# AstableMultivibrator-PNP-old.net
KiCad netlist of a schematic drawn in EAGLE
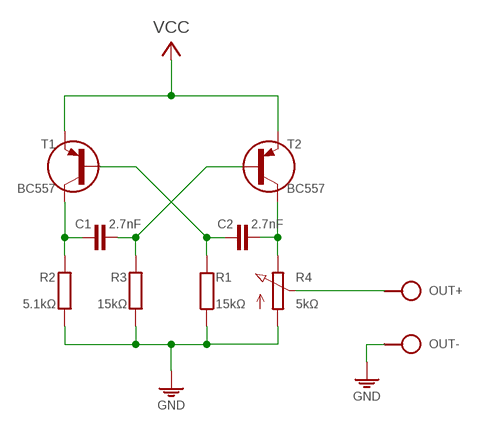
[diagram p0: schematic, sheet 1]

(export (version "E")
  (design (tool "Eeschema 10.0.6"))
  (components
    (comp (ref "C1")
      (value "2.7nF")
      (footprint "eagle-import:C050-020X044")
      (libsource (lib "eagle-import") (part "C-H050-020X044"))
    )
    (comp (ref "C2")
      (value "2.7nF")
      (footprint "eagle-import:C050-020X044")
      (libsource (lib "eagle-import") (part "C-H050-020X044"))
    )
    (comp (ref "J1")
      (value "VCC_GNDPWR-L")
      (footprint "eagle-import:PWR-L")
      (libsource (lib "eagle-import") (part "VCC_GNDPWR-L"))
    )
    (comp (ref "OUT")
      (value "SPAD+--+")
      (footprint "eagle-import:SPAD-+")
      (libsource (lib "eagle-import") (part "SPAD+--+"))
    )
    (comp (ref "R1")
      (value "15kΩ")
      (footprint "eagle-import:0202_5-V")
      (libsource (lib "eagle-import") (part "R0202/5-V"))
    )
    (comp (ref "R2")
      (value "5.1kΩ")
      (footprint "eagle-import:0202_5-V")
      (libsource (lib "eagle-import") (part "R0202/5-V"))
    )
    (comp (ref "R3")
      (value "15kΩ")
      (footprint "eagle-import:0202_5-V")
      (libsource (lib "eagle-import") (part "R0202/5-V"))
    )
    (comp (ref "R4")
      (value "5kΩ")
      (footprint "eagle-import:POT-V")
      (libsource (lib "eagle-import") (part "POT-V"))
    )
    (comp (ref "T1")
      (value "BC557")
      (footprint "eagle-import:TO92-CBE")
      (libsource (lib "eagle-import") (part "BC557CBE"))
    )
    (comp (ref "T2")
      (value "BC557")
      (footprint "eagle-import:TO92-CBE")
      (libsource (lib "eagle-import") (part "BC557CBE"))
    )
  )
  (nets
    (net (code "1") (name "GND") (class "Default")
      (node (ref "J1") (pin "1") (pinfunction "GND_1") (pintype "power_in"))
      (node (ref "OUT") (pin "1") (pinfunction "P$1_1") (pintype "passive"))
      (node (ref "R1") (pin "1") (pinfunction "2_1") (pintype "passive"))
      (node (ref "R2") (pin "1") (pinfunction "2_1") (pintype "passive"))
      (node (ref "R3") (pin "1") (pinfunction "2_1") (pintype "passive"))
      (node (ref "R4") (pin "A") (pinfunction "A_A") (pintype "passive"))
    )
    (net (code "2") (name "Net-(C2-Pad2)") (class "Default")
      (node (ref "C2") (pin "2") (pinfunction "2_2") (pintype "passive"))
      (node (ref "R4") (pin "E") (pinfunction "E_E") (pintype "passive"))
      (node (ref "T2") (pin "C") (pinfunction "C_C") (pintype "passive"))
    )
    (net (code "3") (name "Net-(J1A-VCC)") (class "Default")
      (node (ref "J1") (pin "2") (pinfunction "VCC_2") (pintype "power_in"))
      (node (ref "T1") (pin "E") (pinfunction "E_E") (pintype "passive"))
      (node (ref "T2") (pin "E") (pinfunction "E_E") (pintype "passive"))
    )
    (net (code "4") (name "Net-(OUTA-P$1)") (class "Default")
      (node (ref "OUT") (pin "2") (pinfunction "P$1_2") (pintype "passive"))
      (node (ref "R4") (pin "S") (pinfunction "S_S") (pintype "passive"))
    )
    (net (code "5") (name "Net-(R1-1)") (class "Default")
      (node (ref "C2") (pin "1") (pinfunction "1_1") (pintype "passive"))
      (node (ref "R1") (pin "2") (pinfunction "1_2") (pintype "passive"))
      (node (ref "T1") (pin "B") (pinfunction "B_B") (pintype "passive"))
    )
    (net (code "6") (name "Net-(R2-1)") (class "Default")
      (node (ref "C1") (pin "1") (pinfunction "1_1") (pintype "passive"))
      (node (ref "R2") (pin "2") (pinfunction "1_2") (pintype "passive"))
      (node (ref "T1") (pin "C") (pinfunction "C_C") (pintype "passive"))
    )
    (net (code "7") (name "Net-(R3-1)") (class "Default")
      (node (ref "C1") (pin "2") (pinfunction "2_2") (pintype "passive"))
      (node (ref "R3") (pin "2") (pinfunction "1_2") (pintype "passive"))
      (node (ref "T2") (pin "B") (pinfunction "B_B") (pintype "passive"))
    )
  )
)
